# led.net
KiCad netlist of a schematic drawn in Altium Designer
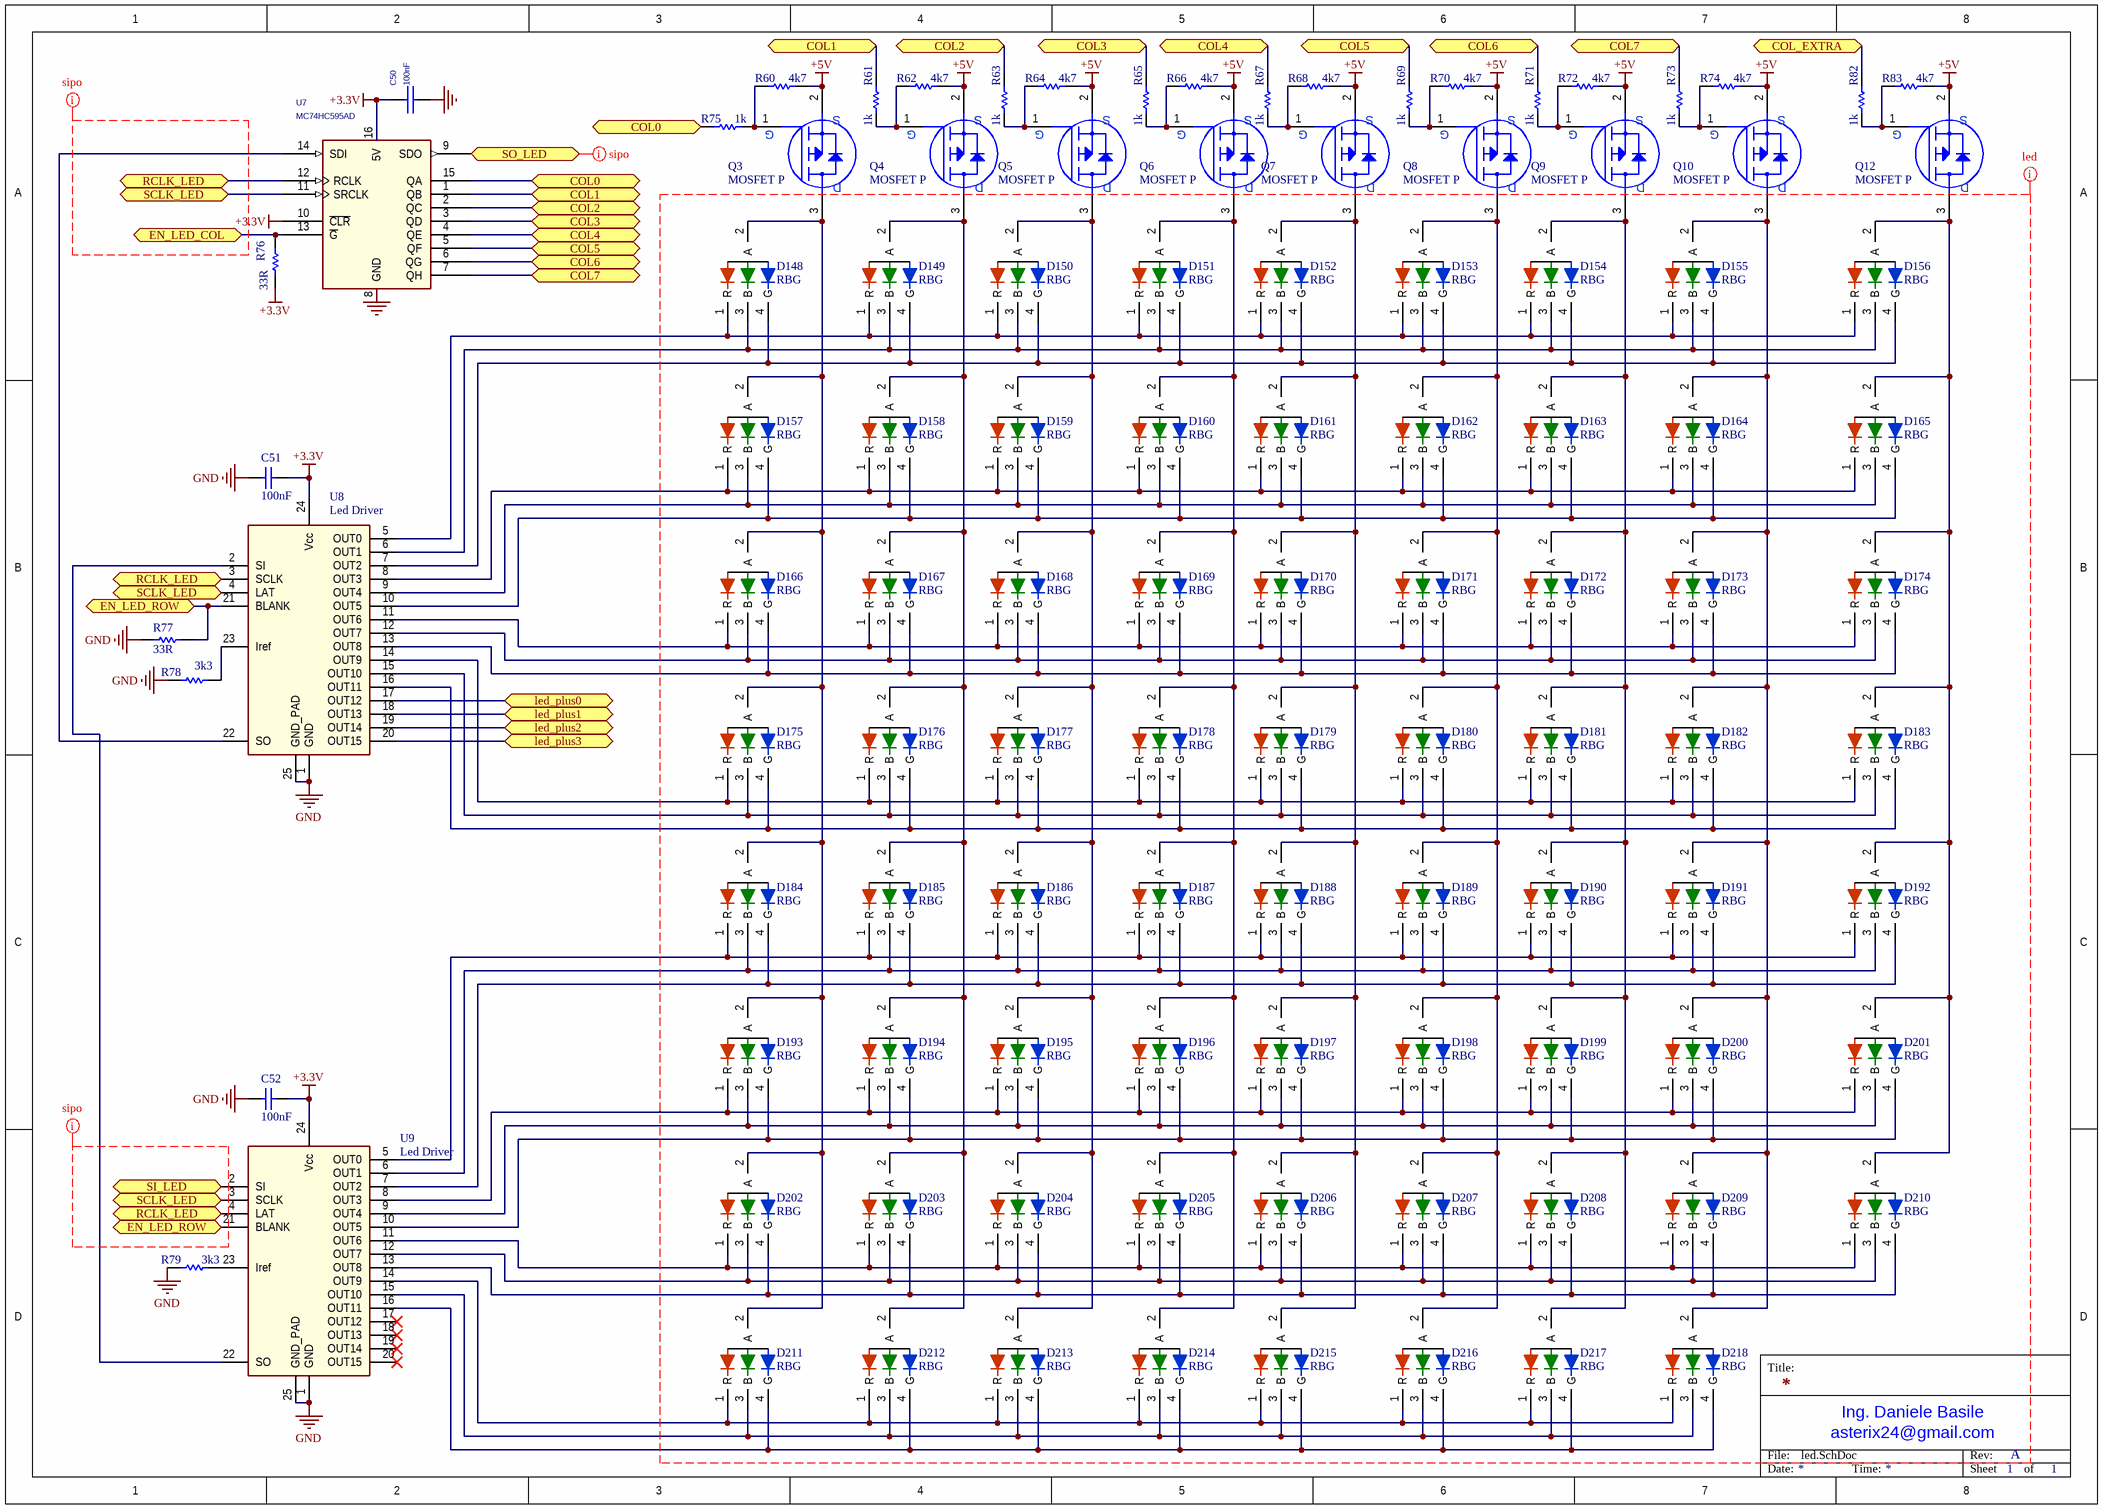
[diagram p0: led.SchDoc]

(export (version "E")
  (design (tool "Eeschema 10.0.6"))
  (components
    (comp (ref "C50")
      (value "100nF")
      (footprint "0603_[1608]")
      (description "CER 50V X7R")
      (libsource (lib "*") (part "C"))
    )
    (comp (ref "C51")
      (value "100nF")
      (footprint "0603_[1608]")
      (description "Ceramic X7R 50V")
      (fields (field (name "PUBLISHER") "Altium Limited"))
      (libsource (lib "DEVELER_Library") (part "Cap"))
    )
    (comp (ref "C52")
      (value "100nF")
      (footprint "0603_[1608]")
      (description "Ceramic X7R 50V")
      (fields (field (name "PUBLISHER") "Altium Limited"))
      (libsource (lib "DEVELER_Library") (part "Cap"))
    )
    (comp (ref "D148")
      (value "RBG")
      (description "Led RGB Thrue Hole")
      (libsource (lib "develer_library") (part "Led_RGB_COM_A_THD"))
    )
    (comp (ref "D149")
      (value "RBG")
      (footprint "led_3.2x2.8mm_4p_smd")
      (description "Led RGB Thrue Hole")
      (libsource (lib "develer_library") (part "Led_RGB_COM_A_THD"))
    )
    (comp (ref "D150")
      (value "RBG")
      (footprint "led_3.2x2.8mm_4p_smd")
      (description "Led RGB Thrue Hole")
      (libsource (lib "develer_library") (part "Led_RGB_COM_A_THD"))
    )
    (comp (ref "D151")
      (value "RBG")
      (footprint "led_3.2x2.8mm_4p_smd")
      (description "Led RGB Thrue Hole")
      (libsource (lib "develer_library") (part "Led_RGB_COM_A_THD"))
    )
    (comp (ref "D152")
      (value "RBG")
      (description "Led RGB Thrue Hole")
      (libsource (lib "develer_library") (part "Led_RGB_COM_A_THD"))
    )
    (comp (ref "D153")
      (value "RBG")
      (footprint "led_3.2x2.8mm_4p_smd")
      (description "Led RGB Thrue Hole")
      (libsource (lib "develer_library") (part "Led_RGB_COM_A_THD"))
    )
    (comp (ref "D154")
      (value "RBG")
      (description "Led RGB Thrue Hole")
      (libsource (lib "develer_library") (part "Led_RGB_COM_A_THD"))
    )
    (comp (ref "D155")
      (value "RBG")
      (description "Led RGB Thrue Hole")
      (libsource (lib "develer_library") (part "Led_RGB_COM_A_THD"))
    )
    (comp (ref "D156")
      (value "RBG")
      (footprint "R3_RGB_LED_THD")
      (description "Led RGB Thrue Hole")
      (libsource (lib "develer_library") (part "Led_RGB_COM_A_THD"))
    )
    (comp (ref "D157")
      (value "RBG")
      (footprint "R3_RGB_LED_THD")
      (description "Led RGB Thrue Hole")
      (libsource (lib "develer_library") (part "Led_RGB_COM_A_THD"))
    )
    (comp (ref "D158")
      (value "RBG")
      (footprint "R3_RGB_LED_THD")
      (description "Led RGB Thrue Hole")
      (libsource (lib "develer_library") (part "Led_RGB_COM_A_THD"))
    )
    (comp (ref "D159")
      (value "RBG")
      (footprint "R3_RGB_LED_THD")
      (description "Led RGB Thrue Hole")
      (libsource (lib "develer_library") (part "Led_RGB_COM_A_THD"))
    )
    (comp (ref "D160")
      (value "RBG")
      (description "Led RGB Thrue Hole")
      (libsource (lib "develer_library") (part "Led_RGB_COM_A_THD"))
    )
    (comp (ref "D161")
      (value "RBG")
      (description "Led RGB Thrue Hole")
      (libsource (lib "develer_library") (part "Led_RGB_COM_A_THD"))
    )
    (comp (ref "D162")
      (value "RBG")
      (description "Led RGB Thrue Hole")
      (libsource (lib "develer_library") (part "Led_RGB_COM_A_THD"))
    )
    (comp (ref "D163")
      (value "RBG")
      (description "Led RGB Thrue Hole")
      (libsource (lib "develer_library") (part "Led_RGB_COM_A_THD"))
    )
    (comp (ref "D164")
      (value "RBG")
      (footprint "led_3.2x2.8mm_4p_smd")
      (description "Led RGB Thrue Hole")
      (libsource (lib "develer_library") (part "Led_RGB_COM_A_THD"))
    )
    (comp (ref "D165")
      (value "RBG")
      (footprint "R3_RGB_LED_THD")
      (description "Led RGB Thrue Hole")
      (libsource (lib "develer_library") (part "Led_RGB_COM_A_THD"))
    )
    (comp (ref "D166")
      (value "RBG")
      (footprint "R3_RGB_LED_THD")
      (description "Led RGB Thrue Hole")
      (libsource (lib "develer_library") (part "Led_RGB_COM_A_THD"))
    )
    (comp (ref "D167")
      (value "RBG")
      (footprint "R3_RGB_LED_THD")
      (description "Led RGB Thrue Hole")
      (libsource (lib "develer_library") (part "Led_RGB_COM_A_THD"))
    )
    (comp (ref "D168")
      (value "RBG")
      (footprint "R3_RGB_LED_THD")
      (description "Led RGB Thrue Hole")
      (libsource (lib "develer_library") (part "Led_RGB_COM_A_THD"))
    )
    (comp (ref "D169")
      (value "RBG")
      (description "Led RGB Thrue Hole")
      (libsource (lib "develer_library") (part "Led_RGB_COM_A_THD"))
    )
    (comp (ref "D170")
      (value "RBG")
      (description "Led RGB Thrue Hole")
      (libsource (lib "develer_library") (part "Led_RGB_COM_A_THD"))
    )
    (comp (ref "D171")
      (value "RBG")
      (description "Led RGB Thrue Hole")
      (libsource (lib "develer_library") (part "Led_RGB_COM_A_THD"))
    )
    (comp (ref "D172")
      (value "RBG")
      (description "Led RGB Thrue Hole")
      (libsource (lib "develer_library") (part "Led_RGB_COM_A_THD"))
    )
    (comp (ref "D173")
      (value "RBG")
      (footprint "R3_RGB_LED_THD")
      (description "Led RGB Thrue Hole")
      (libsource (lib "develer_library") (part "Led_RGB_COM_A_THD"))
    )
    (comp (ref "D174")
      (value "RBG")
      (footprint "R3_RGB_LED_THD")
      (description "Led RGB Thrue Hole")
      (libsource (lib "develer_library") (part "Led_RGB_COM_A_THD"))
    )
    (comp (ref "D175")
      (value "RBG")
      (footprint "R3_RGB_LED_THD")
      (description "Led RGB Thrue Hole")
      (libsource (lib "develer_library") (part "Led_RGB_COM_A_THD"))
    )
    (comp (ref "D176")
      (value "RBG")
      (footprint "R3_RGB_LED_THD")
      (description "Led RGB Thrue Hole")
      (libsource (lib "develer_library") (part "Led_RGB_COM_A_THD"))
    )
    (comp (ref "D177")
      (value "RBG")
      (description "Led RGB Thrue Hole")
      (libsource (lib "develer_library") (part "Led_RGB_COM_A_THD"))
    )
    (comp (ref "D178")
      (value "RBG")
      (description "Led RGB Thrue Hole")
      (libsource (lib "develer_library") (part "Led_RGB_COM_A_THD"))
    )
    (comp (ref "D179")
      (value "RBG")
      (description "Led RGB Thrue Hole")
      (libsource (lib "develer_library") (part "Led_RGB_COM_A_THD"))
    )
    (comp (ref "D180")
      (value "RBG")
      (description "Led RGB Thrue Hole")
      (libsource (lib "develer_library") (part "Led_RGB_COM_A_THD"))
    )
    (comp (ref "D181")
      (value "RBG")
      (footprint "R3_RGB_LED_THD")
      (description "Led RGB Thrue Hole")
      (libsource (lib "develer_library") (part "Led_RGB_COM_A_THD"))
    )
    (comp (ref "D182")
      (value "RBG")
      (footprint "R3_RGB_LED_THD")
      (description "Led RGB Thrue Hole")
      (libsource (lib "develer_library") (part "Led_RGB_COM_A_THD"))
    )
    (comp (ref "D183")
      (value "RBG")
      (footprint "R3_RGB_LED_THD")
      (description "Led RGB Thrue Hole")
      (libsource (lib "develer_library") (part "Led_RGB_COM_A_THD"))
    )
    (comp (ref "D184")
      (value "RBG")
      (footprint "R3_RGB_LED_THD")
      (description "Led RGB Thrue Hole")
      (libsource (lib "develer_library") (part "Led_RGB_COM_A_THD"))
    )
    (comp (ref "D185")
      (value "RBG")
      (description "Led RGB Thrue Hole")
      (libsource (lib "develer_library") (part "Led_RGB_COM_A_THD"))
    )
    (comp (ref "D186")
      (value "RBG")
      (description "Led RGB Thrue Hole")
      (libsource (lib "develer_library") (part "Led_RGB_COM_A_THD"))
    )
    (comp (ref "D187")
      (value "RBG")
      (description "Led RGB Thrue Hole")
      (libsource (lib "develer_library") (part "Led_RGB_COM_A_THD"))
    )
    (comp (ref "D188")
      (value "RBG")
      (description "Led RGB Thrue Hole")
      (libsource (lib "develer_library") (part "Led_RGB_COM_A_THD"))
    )
    (comp (ref "D189")
      (value "RBG")
      (footprint "R3_RGB_LED_THD")
      (description "Led RGB Thrue Hole")
      (libsource (lib "develer_library") (part "Led_RGB_COM_A_THD"))
    )
    (comp (ref "D190")
      (value "RBG")
      (footprint "R3_RGB_LED_THD")
      (description "Led RGB Thrue Hole")
      (libsource (lib "develer_library") (part "Led_RGB_COM_A_THD"))
    )
    (comp (ref "D191")
      (value "RBG")
      (footprint "R3_RGB_LED_THD")
      (description "Led RGB Thrue Hole")
      (libsource (lib "develer_library") (part "Led_RGB_COM_A_THD"))
    )
    (comp (ref "D192")
      (value "RBG")
      (footprint "R3_RGB_LED_THD")
      (description "Led RGB Thrue Hole")
      (libsource (lib "develer_library") (part "Led_RGB_COM_A_THD"))
    )
    (comp (ref "D193")
      (value "RBG")
      (description "Led RGB Thrue Hole")
      (libsource (lib "develer_library") (part "Led_RGB_COM_A_THD"))
    )
    (comp (ref "D194")
      (value "RBG")
      (description "Led RGB Thrue Hole")
      (libsource (lib "develer_library") (part "Led_RGB_COM_A_THD"))
    )
    (comp (ref "D195")
      (value "RBG")
      (description "Led RGB Thrue Hole")
      (libsource (lib "develer_library") (part "Led_RGB_COM_A_THD"))
    )
    (comp (ref "D196")
      (value "RBG")
      (description "Led RGB Thrue Hole")
      (libsource (lib "develer_library") (part "Led_RGB_COM_A_THD"))
    )
    (comp (ref "D197")
      (value "RBG")
      (footprint "R3_RGB_LED_THD")
      (description "Led RGB Thrue Hole")
      (libsource (lib "develer_library") (part "Led_RGB_COM_A_THD"))
    )
    (comp (ref "D198")
      (value "RBG")
      (footprint "R3_RGB_LED_THD")
      (description "Led RGB Thrue Hole")
      (libsource (lib "develer_library") (part "Led_RGB_COM_A_THD"))
    )
    (comp (ref "D199")
      (value "RBG")
      (footprint "R3_RGB_LED_THD")
      (description "Led RGB Thrue Hole")
      (libsource (lib "develer_library") (part "Led_RGB_COM_A_THD"))
    )
    (comp (ref "D200")
      (value "RBG")
      (footprint "led_3.2x2.8mm_4p_smd")
      (description "Led RGB Thrue Hole")
      (libsource (lib "develer_library") (part "Led_RGB_COM_A_THD"))
    )
    (comp (ref "D201")
      (value "RBG")
      (footprint "R3_RGB_LED_THD")
      (description "Led RGB Thrue Hole")
      (libsource (lib "develer_library") (part "Led_RGB_COM_A_THD"))
    )
    (comp (ref "D202")
      (value "RBG")
      (description "Led RGB Thrue Hole")
      (libsource (lib "develer_library") (part "Led_RGB_COM_A_THD"))
    )
    (comp (ref "D203")
      (value "RBG")
      (description "Led RGB Thrue Hole")
      (libsource (lib "develer_library") (part "Led_RGB_COM_A_THD"))
    )
    (comp (ref "D204")
      (value "RBG")
      (description "Led RGB Thrue Hole")
      (libsource (lib "develer_library") (part "Led_RGB_COM_A_THD"))
    )
    (comp (ref "D205")
      (value "RBG")
      (description "Led RGB Thrue Hole")
      (libsource (lib "develer_library") (part "Led_RGB_COM_A_THD"))
    )
    (comp (ref "D206")
      (value "RBG")
      (footprint "R3_RGB_LED_THD")
      (description "Led RGB Thrue Hole")
      (libsource (lib "develer_library") (part "Led_RGB_COM_A_THD"))
    )
    (comp (ref "D207")
      (value "RBG")
      (footprint "R3_RGB_LED_THD")
      (description "Led RGB Thrue Hole")
      (libsource (lib "develer_library") (part "Led_RGB_COM_A_THD"))
    )
    (comp (ref "D208")
      (value "RBG")
      (footprint "R3_RGB_LED_THD")
      (description "Led RGB Thrue Hole")
      (libsource (lib "develer_library") (part "Led_RGB_COM_A_THD"))
    )
    (comp (ref "D209")
      (value "RBG")
      (footprint "R3_RGB_LED_THD")
      (description "Led RGB Thrue Hole")
      (libsource (lib "develer_library") (part "Led_RGB_COM_A_THD"))
    )
    (comp (ref "D210")
      (value "RBG")
      (description "Led RGB Thrue Hole")
      (libsource (lib "develer_library") (part "Led_RGB_COM_A_THD"))
    )
    (comp (ref "D211")
      (value "RBG")
      (description "Led RGB Thrue Hole")
      (libsource (lib "develer_library") (part "Led_RGB_COM_A_THD"))
    )
    (comp (ref "D212")
      (value "RBG")
      (footprint "R3_RGB_LED_THD")
      (description "Led RGB Thrue Hole")
      (libsource (lib "develer_library") (part "Led_RGB_COM_A_THD"))
    )
    (comp (ref "D213")
      (value "RBG")
      (footprint "R3_RGB_LED_THD")
      (description "Led RGB Thrue Hole")
      (libsource (lib "develer_library") (part "Led_RGB_COM_A_THD"))
    )
    (comp (ref "D214")
      (value "RBG")
      (footprint "R3_RGB_LED_THD")
      (description "Led RGB Thrue Hole")
      (libsource (lib "develer_library") (part "Led_RGB_COM_A_THD"))
    )
    (comp (ref "D215")
      (value "RBG")
      (footprint "R3_RGB_LED_THD")
      (description "Led RGB Thrue Hole")
      (libsource (lib "develer_library") (part "Led_RGB_COM_A_THD"))
    )
    (comp (ref "D216")
      (value "RBG")
      (footprint "R3_RGB_LED_THD")
      (description "Led RGB Thrue Hole")
      (libsource (lib "develer_library") (part "Led_RGB_COM_A_THD"))
    )
    (comp (ref "D217")
      (value "RBG")
      (footprint "R3_RGB_LED_THD")
      (description "Led RGB Thrue Hole")
      (libsource (lib "develer_library") (part "Led_RGB_COM_A_THD"))
    )
    (comp (ref "D218")
      (value "RBG")
      (footprint "R3_RGB_LED_THD")
      (description "Led RGB Thrue Hole")
      (libsource (lib "develer_library") (part "Led_RGB_COM_A_THD"))
    )
    (comp (ref "Q3")
      (value "MOSFET P")
      (footprint "SOT-23")
      (description "IRLML5103TRPbF; DMG1013UW;")
      (libsource (lib "develer_library") (part "MOSFET-P 3pin"))
    )
    (comp (ref "Q4")
      (value "MOSFET P")
      (footprint "SOT-23")
      (libsource (lib "develer_library") (part "MOSFET-P 3pin"))
    )
    (comp (ref "Q5")
      (value "MOSFET P")
      (footprint "SOT-23")
      (libsource (lib "develer_library") (part "MOSFET-P 3pin"))
    )
    (comp (ref "Q6")
      (value "MOSFET P")
      (footprint "SOT-23")
      (libsource (lib "develer_library") (part "MOSFET-P 3pin"))
    )
    (comp (ref "Q7")
      (value "MOSFET P")
      (footprint "SOT-23")
      (libsource (lib "develer_library") (part "MOSFET-P 3pin"))
    )
    (comp (ref "Q8")
      (value "MOSFET P")
      (footprint "SOT-23")
      (libsource (lib "develer_library") (part "MOSFET-P 3pin"))
    )
    (comp (ref "Q9")
      (value "MOSFET P")
      (footprint "SOT-23")
      (libsource (lib "develer_library") (part "MOSFET-P 3pin"))
    )
    (comp (ref "Q10")
      (value "MOSFET P")
      (footprint "SOT-23")
      (libsource (lib "develer_library") (part "MOSFET-P 3pin"))
    )
    (comp (ref "Q12")
      (value "MOSFET P")
      (footprint "SOT-23")
      (libsource (lib "develer_library") (part "MOSFET-P 3pin"))
    )
    (comp (ref "R60")
      (value "4k7")
      (footprint "0603_[1608]")
      (description "Resistor")
      (fields (field (name "PUBLISHER") "Altium Limited"))
      (libsource (lib "simboli") (part "Res1"))
    )
    (comp (ref "R61")
      (value "1k")
      (footprint "0603_[1608]")
      (description "Resistor")
      (fields (field (name "PUBLISHER") "Altium Limited"))
      (libsource (lib "simboli") (part "Res1"))
    )
    (comp (ref "R62")
      (value "4k7")
      (footprint "0603_[1608]")
      (description "Resistor")
      (fields (field (name "PUBLISHER") "Altium Limited"))
      (libsource (lib "simboli") (part "Res1"))
    )
    (comp (ref "R63")
      (value "1k")
      (footprint "0603_[1608]")
      (description "Resistor")
      (fields (field (name "PUBLISHER") "Altium Limited"))
      (libsource (lib "simboli") (part "Res1"))
    )
    (comp (ref "R64")
      (value "4k7")
      (footprint "0603_[1608]")
      (description "Resistor")
      (fields (field (name "PUBLISHER") "Altium Limited"))
      (libsource (lib "simboli") (part "Res1"))
    )
    (comp (ref "R65")
      (value "1k")
      (footprint "0603_[1608]")
      (description "Resistor")
      (fields (field (name "PUBLISHER") "Altium Limited"))
      (libsource (lib "simboli") (part "Res1"))
    )
    (comp (ref "R66")
      (value "4k7")
      (footprint "0603_[1608]")
      (description "Resistor")
      (fields (field (name "PUBLISHER") "Altium Limited"))
      (libsource (lib "simboli") (part "Res1"))
    )
    (comp (ref "R67")
      (value "1k")
      (footprint "0603_[1608]")
      (description "Resistor")
      (fields (field (name "PUBLISHER") "Altium Limited"))
      (libsource (lib "simboli") (part "Res1"))
    )
    (comp (ref "R68")
      (value "4k7")
      (footprint "0603_[1608]")
      (description "Resistor")
      (fields (field (name "PUBLISHER") "Altium Limited"))
      (libsource (lib "simboli") (part "Res1"))
    )
    (comp (ref "R69")
      (value "1k")
      (footprint "0603_[1608]")
      (description "Resistor")
      (fields (field (name "PUBLISHER") "Altium Limited"))
      (libsource (lib "simboli") (part "Res1"))
    )
    (comp (ref "R70")
      (value "4k7")
      (footprint "0603_[1608]")
      (description "Resistor")
      (fields (field (name "PUBLISHER") "Altium Limited"))
      (libsource (lib "simboli") (part "Res1"))
    )
    (comp (ref "R71")
      (value "1k")
      (footprint "0603_[1608]")
      (description "Resistor")
      (fields (field (name "PUBLISHER") "Altium Limited"))
      (libsource (lib "simboli") (part "Res1"))
    )
    (comp (ref "R72")
      (value "4k7")
      (footprint "0603_[1608]")
      (description "Resistor")
      (fields (field (name "PUBLISHER") "Altium Limited"))
      (libsource (lib "simboli") (part "Res1"))
    )
    (comp (ref "R73")
      (value "1k")
      (footprint "0603_[1608]")
      (description "Resistor")
      (fields (field (name "PUBLISHER") "Altium Limited"))
      (libsource (lib "simboli") (part "Res1"))
    )
    (comp (ref "R74")
      (value "4k7")
      (footprint "0603_[1608]")
      (description "Resistor")
      (fields (field (name "PUBLISHER") "Altium Limited"))
      (libsource (lib "simboli") (part "Res1"))
    )
    (comp (ref "R75")
      (value "1k")
      (footprint "0603_[1608]")
      (description "Resistor")
      (fields (field (name "PUBLISHER") "Altium Limited"))
      (libsource (lib "simboli") (part "Res1"))
    )
    (comp (ref "R76")
      (value "33R")
      (footprint "0603_[1608]")
      (description "Resistor")
      (fields (field (name "PUBLISHER") "Altium Limited"))
      (libsource (lib "simboli") (part "Res1"))
    )
    (comp (ref "R77")
      (value "33R")
      (footprint "0603_[1608]")
      (description "Resistor")
      (fields (field (name "PUBLISHER") "Altium Limited"))
      (libsource (lib "simboli") (part "Res1"))
    )
    (comp (ref "R78")
      (value "3k3")
      (footprint "0805_[2012]")
      (description "Resistor")
      (fields (field (name "PUBLISHER") "Altium Limited"))
      (libsource (lib "simboli") (part "Res1"))
    )
    (comp (ref "R79")
      (value "3k3")
      (footprint "0805_[2012]")
      (description "Resistor")
      (fields (field (name "PUBLISHER") "Altium Limited"))
      (libsource (lib "simboli") (part "Res1"))
    )
    (comp (ref "R82")
      (value "1k")
      (footprint "0603_[1608]")
      (description "Resistor")
      (fields (field (name "PUBLISHER") "Altium Limited"))
      (libsource (lib "simboli") (part "Res1"))
    )
    (comp (ref "R83")
      (value "4k7")
      (footprint "0603_[1608]")
      (description "Resistor")
      (fields (field (name "PUBLISHER") "Altium Limited"))
      (libsource (lib "simboli") (part "Res1"))
    )
    (comp (ref "U7")
      (value "MC74HC595AD")
      (footprint "SOIC16")
      (description "8-Bit Serial-Input/Serial or Prallel-Output Shift Register with Latched 3-State Outputs")
      (libsource (lib "*") (part "74HC595_27"))
    )
    (comp (ref "U8")
      (value "Led Driver")
      (footprint "TSOP65P640X120_HS-25N")
      (description "(Texas TLC5928; ST STP16CP05)")
      (libsource (lib "develer_library") (part "Led_driver"))
    )
    (comp (ref "U9")
      (value "Led Driver")
      (footprint "TSOP65P640X120_HS-25N")
      (description "(Texas TLC5928; ST STP16CP05)")
      (libsource (lib "develer_library") (part "Led_driver"))
    )
  )
  (nets
    (net (code "1") (name "+3.3V") (class "Default")
      (node (ref "C50") (pin "1") (pinfunction "1_1") (pintype "passive"))
      (node (ref "C51") (pin "2") (pinfunction "2_2") (pintype "passive"))
      (node (ref "C52") (pin "2") (pinfunction "2_2") (pintype "passive"))
      (node (ref "R76") (pin "1") (pinfunction "1_1") (pintype "passive"))
      (node (ref "U7") (pin "10") (pinfunction "~{CLR}_10") (pintype "passive"))
      (node (ref "U7") (pin "16") (pinfunction "5V_16") (pintype "power_in"))
      (node (ref "U8") (pin "24") (pinfunction "Vcc_24") (pintype "passive"))
      (node (ref "U9") (pin "24") (pinfunction "Vcc_24") (pintype "passive"))
    )
    (net (code "2") (name "+5V") (class "Default")
      (node (ref "Q10") (pin "2") (pinfunction "S_2") (pintype "passive"))
      (node (ref "Q12") (pin "2") (pinfunction "S_2") (pintype "passive"))
      (node (ref "Q3") (pin "2") (pinfunction "S_2") (pintype "passive"))
      (node (ref "Q4") (pin "2") (pinfunction "S_2") (pintype "passive"))
      (node (ref "Q5") (pin "2") (pinfunction "S_2") (pintype "passive"))
      (node (ref "Q6") (pin "2") (pinfunction "S_2") (pintype "passive"))
      (node (ref "Q7") (pin "2") (pinfunction "S_2") (pintype "passive"))
      (node (ref "Q8") (pin "2") (pinfunction "S_2") (pintype "passive"))
      (node (ref "Q9") (pin "2") (pinfunction "S_2") (pintype "passive"))
      (node (ref "R60") (pin "1") (pinfunction "1_1") (pintype "passive"))
      (node (ref "R62") (pin "1") (pinfunction "1_1") (pintype "passive"))
      (node (ref "R64") (pin "1") (pinfunction "1_1") (pintype "passive"))
      (node (ref "R66") (pin "1") (pinfunction "1_1") (pintype "passive"))
      (node (ref "R68") (pin "1") (pinfunction "1_1") (pintype "passive"))
      (node (ref "R70") (pin "1") (pinfunction "1_1") (pintype "passive"))
      (node (ref "R72") (pin "1") (pinfunction "1_1") (pintype "passive"))
      (node (ref "R74") (pin "1") (pinfunction "1_1") (pintype "passive"))
      (node (ref "R83") (pin "1") (pinfunction "1_1") (pintype "passive"))
    )
    (net (code "3") (name "/COL0") (class "Default")
      (node (ref "R75") (pin "2") (pinfunction "2_2") (pintype "passive"))
      (node (ref "U7") (pin "15") (pinfunction "QA_15") (pintype "tri_state"))
    )
    (net (code "4") (name "/COL1") (class "Default")
      (node (ref "R61") (pin "1") (pinfunction "1_1") (pintype "passive"))
      (node (ref "U7") (pin "1") (pinfunction "QB_1") (pintype "tri_state"))
    )
    (net (code "5") (name "/COL2") (class "Default")
      (node (ref "R63") (pin "1") (pinfunction "1_1") (pintype "passive"))
      (node (ref "U7") (pin "2") (pinfunction "QC_2") (pintype "tri_state"))
    )
    (net (code "6") (name "/COL3") (class "Default")
      (node (ref "R65") (pin "1") (pinfunction "1_1") (pintype "passive"))
      (node (ref "U7") (pin "3") (pinfunction "QD_3") (pintype "tri_state"))
    )
    (net (code "7") (name "/COL4") (class "Default")
      (node (ref "R67") (pin "1") (pinfunction "1_1") (pintype "passive"))
      (node (ref "U7") (pin "4") (pinfunction "QE_4") (pintype "tri_state"))
    )
    (net (code "8") (name "/COL5") (class "Default")
      (node (ref "R69") (pin "1") (pinfunction "1_1") (pintype "passive"))
      (node (ref "U7") (pin "5") (pinfunction "QF_5") (pintype "tri_state"))
    )
    (net (code "9") (name "/COL6") (class "Default")
      (node (ref "R71") (pin "1") (pinfunction "1_1") (pintype "passive"))
      (node (ref "U7") (pin "6") (pinfunction "QG_6") (pintype "tri_state"))
    )
    (net (code "10") (name "/COL7") (class "Default")
      (node (ref "R73") (pin "1") (pinfunction "1_1") (pintype "passive"))
      (node (ref "U7") (pin "7") (pinfunction "QH_7") (pintype "tri_state"))
    )
    (net (code "11") (name "/COL_EXTRA") (class "Default")
      (node (ref "R82") (pin "1") (pinfunction "1_1") (pintype "passive"))
    )
    (net (code "12") (name "/EN_LED_COL") (class "Default")
      (node (ref "R76") (pin "2") (pinfunction "2_2") (pintype "passive"))
      (node (ref "U7") (pin "13") (pinfunction "~{G}_13") (pintype "passive"))
    )
    (net (code "13") (name "/EN_LED_ROW") (class "Default")
      (node (ref "R77") (pin "2") (pinfunction "2_2") (pintype "passive"))
      (node (ref "U8") (pin "21") (pinfunction "BLANK_21") (pintype "passive"))
      (node (ref "U9") (pin "21") (pinfunction "BLANK_21") (pintype "passive"))
    )
    (net (code "14") (name "/RCLK_LED") (class "Default")
      (node (ref "U7") (pin "12") (pinfunction "RCLK_12") (pintype "input"))
      (node (ref "U8") (pin "3") (pinfunction "SCLK_3") (pintype "passive"))
      (node (ref "U9") (pin "4") (pinfunction "LAT_4") (pintype "passive"))
    )
    (net (code "15") (name "/SCLK_LED") (class "Default")
      (node (ref "U7") (pin "11") (pinfunction "SRCLK_11") (pintype "input"))
      (node (ref "U8") (pin "4") (pinfunction "LAT_4") (pintype "passive"))
      (node (ref "U9") (pin "3") (pinfunction "SCLK_3") (pintype "passive"))
    )
    (net (code "16") (name "/SI_LED") (class "Default")
      (node (ref "U9") (pin "2") (pinfunction "SI_2") (pintype "passive"))
    )
    (net (code "17") (name "/SO_LED") (class "Default")
      (node (ref "U7") (pin "9") (pinfunction "SDO_9") (pintype "output"))
    )
    (net (code "18") (name "/led_plus0") (class "Default")
      (node (ref "U8") (pin "17") (pinfunction "OUT12_17") (pintype "passive"))
    )
    (net (code "19") (name "/led_plus1") (class "Default")
      (node (ref "U8") (pin "18") (pinfunction "OUT13_18") (pintype "passive"))
    )
    (net (code "20") (name "/led_plus2") (class "Default")
      (node (ref "U8") (pin "19") (pinfunction "OUT14_19") (pintype "passive"))
    )
    (net (code "21") (name "/led_plus3") (class "Default")
      (node (ref "U8") (pin "20") (pinfunction "OUT15_20") (pintype "passive"))
    )
    (net (code "22") (name "GND") (class "Default")
      (node (ref "C50") (pin "2") (pinfunction "2_2") (pintype "passive"))
      (node (ref "C51") (pin "1") (pinfunction "1_1") (pintype "passive"))
      (node (ref "C52") (pin "1") (pinfunction "1_1") (pintype "passive"))
      (node (ref "R77") (pin "1") (pinfunction "1_1") (pintype "passive"))
      (node (ref "R78") (pin "1") (pinfunction "1_1") (pintype "passive"))
      (node (ref "R79") (pin "1") (pinfunction "1_1") (pintype "passive"))
      (node (ref "U7") (pin "8") (pinfunction "GND_8") (pintype "power_in"))
      (node (ref "U8") (pin "1") (pinfunction "GND_1") (pintype "passive"))
      (node (ref "U8") (pin "25") (pinfunction "GND_PAD_25") (pintype "passive"))
      (node (ref "U9") (pin "1") (pinfunction "GND_1") (pintype "passive"))
      (node (ref "U9") (pin "25") (pinfunction "GND_PAD_25") (pintype "passive"))
    )
    (net (code "23") (name "Net-(D148-A)") (class "Default")
      (node (ref "D148") (pin "2") (pinfunction "A_2") (pintype "passive"))
      (node (ref "D157") (pin "2") (pinfunction "A_2") (pintype "passive"))
      (node (ref "D166") (pin "2") (pinfunction "A_2") (pintype "passive"))
      (node (ref "D175") (pin "2") (pinfunction "A_2") (pintype "passive"))
      (node (ref "D184") (pin "2") (pinfunction "A_2") (pintype "passive"))
      (node (ref "D193") (pin "2") (pinfunction "A_2") (pintype "passive"))
      (node (ref "D202") (pin "2") (pinfunction "A_2") (pintype "passive"))
      (node (ref "D211") (pin "2") (pinfunction "A_2") (pintype "passive"))
      (node (ref "Q3") (pin "3") (pinfunction "D_3") (pintype "passive"))
    )
    (net (code "24") (name "Net-(D148-B)") (class "Default")
      (node (ref "D148") (pin "3") (pinfunction "B_3") (pintype "passive"))
      (node (ref "D149") (pin "3") (pinfunction "B_3") (pintype "passive"))
      (node (ref "D150") (pin "3") (pinfunction "B_3") (pintype "passive"))
      (node (ref "D151") (pin "3") (pinfunction "B_3") (pintype "passive"))
      (node (ref "D152") (pin "3") (pinfunction "B_3") (pintype "passive"))
      (node (ref "D153") (pin "3") (pinfunction "B_3") (pintype "passive"))
      (node (ref "D154") (pin "3") (pinfunction "B_3") (pintype "passive"))
      (node (ref "D155") (pin "3") (pinfunction "B_3") (pintype "passive"))
      (node (ref "D156") (pin "3") (pinfunction "B_3") (pintype "passive"))
      (node (ref "U8") (pin "6") (pinfunction "OUT1_6") (pintype "passive"))
    )
    (net (code "25") (name "Net-(D148-G)") (class "Default")
      (node (ref "D148") (pin "4") (pinfunction "G_4") (pintype "passive"))
      (node (ref "D149") (pin "4") (pinfunction "G_4") (pintype "passive"))
      (node (ref "D150") (pin "4") (pinfunction "G_4") (pintype "passive"))
      (node (ref "D151") (pin "4") (pinfunction "G_4") (pintype "passive"))
      (node (ref "D152") (pin "4") (pinfunction "G_4") (pintype "passive"))
      (node (ref "D153") (pin "4") (pinfunction "G_4") (pintype "passive"))
      (node (ref "D154") (pin "4") (pinfunction "G_4") (pintype "passive"))
      (node (ref "D155") (pin "4") (pinfunction "G_4") (pintype "passive"))
      (node (ref "D156") (pin "4") (pinfunction "G_4") (pintype "passive"))
      (node (ref "U8") (pin "7") (pinfunction "OUT2_7") (pintype "passive"))
    )
    (net (code "26") (name "Net-(D148-R)") (class "Default")
      (node (ref "D148") (pin "1") (pinfunction "R_1") (pintype "passive"))
      (node (ref "D149") (pin "1") (pinfunction "R_1") (pintype "passive"))
      (node (ref "D150") (pin "1") (pinfunction "R_1") (pintype "passive"))
      (node (ref "D151") (pin "1") (pinfunction "R_1") (pintype "passive"))
      (node (ref "D152") (pin "1") (pinfunction "R_1") (pintype "passive"))
      (node (ref "D153") (pin "1") (pinfunction "R_1") (pintype "passive"))
      (node (ref "D154") (pin "1") (pinfunction "R_1") (pintype "passive"))
      (node (ref "D155") (pin "1") (pinfunction "R_1") (pintype "passive"))
      (node (ref "D156") (pin "1") (pinfunction "R_1") (pintype "passive"))
      (node (ref "U8") (pin "5") (pinfunction "OUT0_5") (pintype "passive"))
    )
    (net (code "27") (name "Net-(D149-A)") (class "Default")
      (node (ref "D149") (pin "2") (pinfunction "A_2") (pintype "passive"))
      (node (ref "D158") (pin "2") (pinfunction "A_2") (pintype "passive"))
      (node (ref "D167") (pin "2") (pinfunction "A_2") (pintype "passive"))
      (node (ref "D176") (pin "2") (pinfunction "A_2") (pintype "passive"))
      (node (ref "D185") (pin "2") (pinfunction "A_2") (pintype "passive"))
      (node (ref "D194") (pin "2") (pinfunction "A_2") (pintype "passive"))
      (node (ref "D203") (pin "2") (pinfunction "A_2") (pintype "passive"))
      (node (ref "D212") (pin "2") (pinfunction "A_2") (pintype "passive"))
      (node (ref "Q4") (pin "3") (pinfunction "D_3") (pintype "passive"))
    )
    (net (code "28") (name "Net-(D150-A)") (class "Default")
      (node (ref "D150") (pin "2") (pinfunction "A_2") (pintype "passive"))
      (node (ref "D159") (pin "2") (pinfunction "A_2") (pintype "passive"))
      (node (ref "D168") (pin "2") (pinfunction "A_2") (pintype "passive"))
      (node (ref "D177") (pin "2") (pinfunction "A_2") (pintype "passive"))
      (node (ref "D186") (pin "2") (pinfunction "A_2") (pintype "passive"))
      (node (ref "D195") (pin "2") (pinfunction "A_2") (pintype "passive"))
      (node (ref "D204") (pin "2") (pinfunction "A_2") (pintype "passive"))
      (node (ref "D213") (pin "2") (pinfunction "A_2") (pintype "passive"))
      (node (ref "Q5") (pin "3") (pinfunction "D_3") (pintype "passive"))
    )
    (net (code "29") (name "Net-(D151-A)") (class "Default")
      (node (ref "D151") (pin "2") (pinfunction "A_2") (pintype "passive"))
      (node (ref "D160") (pin "2") (pinfunction "A_2") (pintype "passive"))
      (node (ref "D169") (pin "2") (pinfunction "A_2") (pintype "passive"))
      (node (ref "D178") (pin "2") (pinfunction "A_2") (pintype "passive"))
      (node (ref "D187") (pin "2") (pinfunction "A_2") (pintype "passive"))
      (node (ref "D196") (pin "2") (pinfunction "A_2") (pintype "passive"))
      (node (ref "D205") (pin "2") (pinfunction "A_2") (pintype "passive"))
      (node (ref "D214") (pin "2") (pinfunction "A_2") (pintype "passive"))
      (node (ref "Q6") (pin "3") (pinfunction "D_3") (pintype "passive"))
    )
    (net (code "30") (name "Net-(D152-A)") (class "Default")
      (node (ref "D152") (pin "2") (pinfunction "A_2") (pintype "passive"))
      (node (ref "D161") (pin "2") (pinfunction "A_2") (pintype "passive"))
      (node (ref "D170") (pin "2") (pinfunction "A_2") (pintype "passive"))
      (node (ref "D179") (pin "2") (pinfunction "A_2") (pintype "passive"))
      (node (ref "D188") (pin "2") (pinfunction "A_2") (pintype "passive"))
      (node (ref "D197") (pin "2") (pinfunction "A_2") (pintype "passive"))
      (node (ref "D206") (pin "2") (pinfunction "A_2") (pintype "passive"))
      (node (ref "D215") (pin "2") (pinfunction "A_2") (pintype "passive"))
      (node (ref "Q7") (pin "3") (pinfunction "D_3") (pintype "passive"))
    )
    (net (code "31") (name "Net-(D153-A)") (class "Default")
      (node (ref "D153") (pin "2") (pinfunction "A_2") (pintype "passive"))
      (node (ref "D162") (pin "2") (pinfunction "A_2") (pintype "passive"))
      (node (ref "D171") (pin "2") (pinfunction "A_2") (pintype "passive"))
      (node (ref "D180") (pin "2") (pinfunction "A_2") (pintype "passive"))
      (node (ref "D189") (pin "2") (pinfunction "A_2") (pintype "passive"))
      (node (ref "D198") (pin "2") (pinfunction "A_2") (pintype "passive"))
      (node (ref "D207") (pin "2") (pinfunction "A_2") (pintype "passive"))
      (node (ref "D216") (pin "2") (pinfunction "A_2") (pintype "passive"))
      (node (ref "Q8") (pin "3") (pinfunction "D_3") (pintype "passive"))
    )
    (net (code "32") (name "Net-(D154-A)") (class "Default")
      (node (ref "D154") (pin "2") (pinfunction "A_2") (pintype "passive"))
      (node (ref "D163") (pin "2") (pinfunction "A_2") (pintype "passive"))
      (node (ref "D172") (pin "2") (pinfunction "A_2") (pintype "passive"))
      (node (ref "D181") (pin "2") (pinfunction "A_2") (pintype "passive"))
      (node (ref "D190") (pin "2") (pinfunction "A_2") (pintype "passive"))
      (node (ref "D199") (pin "2") (pinfunction "A_2") (pintype "passive"))
      (node (ref "D208") (pin "2") (pinfunction "A_2") (pintype "passive"))
      (node (ref "D217") (pin "2") (pinfunction "A_2") (pintype "passive"))
      (node (ref "Q9") (pin "3") (pinfunction "D_3") (pintype "passive"))
    )
    (net (code "33") (name "Net-(D155-A)") (class "Default")
      (node (ref "D155") (pin "2") (pinfunction "A_2") (pintype "passive"))
      (node (ref "D164") (pin "2") (pinfunction "A_2") (pintype "passive"))
      (node (ref "D173") (pin "2") (pinfunction "A_2") (pintype "passive"))
      (node (ref "D182") (pin "2") (pinfunction "A_2") (pintype "passive"))
      (node (ref "D191") (pin "2") (pinfunction "A_2") (pintype "passive"))
      (node (ref "D200") (pin "2") (pinfunction "A_2") (pintype "passive"))
      (node (ref "D209") (pin "2") (pinfunction "A_2") (pintype "passive"))
      (node (ref "D218") (pin "2") (pinfunction "A_2") (pintype "passive"))
      (node (ref "Q10") (pin "3") (pinfunction "D_3") (pintype "passive"))
    )
    (net (code "34") (name "Net-(D156-A)") (class "Default")
      (node (ref "D156") (pin "2") (pinfunction "A_2") (pintype "passive"))
      (node (ref "D165") (pin "2") (pinfunction "A_2") (pintype "passive"))
      (node (ref "D174") (pin "2") (pinfunction "A_2") (pintype "passive"))
      (node (ref "D183") (pin "2") (pinfunction "A_2") (pintype "passive"))
      (node (ref "D192") (pin "2") (pinfunction "A_2") (pintype "passive"))
      (node (ref "D201") (pin "2") (pinfunction "A_2") (pintype "passive"))
      (node (ref "D210") (pin "2") (pinfunction "A_2") (pintype "passive"))
      (node (ref "Q12") (pin "3") (pinfunction "D_3") (pintype "passive"))
    )
    (net (code "35") (name "Net-(D157-B)") (class "Default")
      (node (ref "D157") (pin "3") (pinfunction "B_3") (pintype "passive"))
      (node (ref "D158") (pin "3") (pinfunction "B_3") (pintype "passive"))
      (node (ref "D159") (pin "3") (pinfunction "B_3") (pintype "passive"))
      (node (ref "D160") (pin "3") (pinfunction "B_3") (pintype "passive"))
      (node (ref "D161") (pin "3") (pinfunction "B_3") (pintype "passive"))
      (node (ref "D162") (pin "3") (pinfunction "B_3") (pintype "passive"))
      (node (ref "D163") (pin "3") (pinfunction "B_3") (pintype "passive"))
      (node (ref "D164") (pin "3") (pinfunction "B_3") (pintype "passive"))
      (node (ref "D165") (pin "3") (pinfunction "B_3") (pintype "passive"))
      (node (ref "U8") (pin "9") (pinfunction "OUT4_9") (pintype "passive"))
    )
    (net (code "36") (name "Net-(D157-G)") (class "Default")
      (node (ref "D157") (pin "4") (pinfunction "G_4") (pintype "passive"))
      (node (ref "D158") (pin "4") (pinfunction "G_4") (pintype "passive"))
      (node (ref "D159") (pin "4") (pinfunction "G_4") (pintype "passive"))
      (node (ref "D160") (pin "4") (pinfunction "G_4") (pintype "passive"))
      (node (ref "D161") (pin "4") (pinfunction "G_4") (pintype "passive"))
      (node (ref "D162") (pin "4") (pinfunction "G_4") (pintype "passive"))
      (node (ref "D163") (pin "4") (pinfunction "G_4") (pintype "passive"))
      (node (ref "D164") (pin "4") (pinfunction "G_4") (pintype "passive"))
      (node (ref "D165") (pin "4") (pinfunction "G_4") (pintype "passive"))
      (node (ref "U8") (pin "10") (pinfunction "OUT5_10") (pintype "passive"))
    )
    (net (code "37") (name "Net-(D157-R)") (class "Default")
      (node (ref "D157") (pin "1") (pinfunction "R_1") (pintype "passive"))
      (node (ref "D158") (pin "1") (pinfunction "R_1") (pintype "passive"))
      (node (ref "D159") (pin "1") (pinfunction "R_1") (pintype "passive"))
      (node (ref "D160") (pin "1") (pinfunction "R_1") (pintype "passive"))
      (node (ref "D161") (pin "1") (pinfunction "R_1") (pintype "passive"))
      (node (ref "D162") (pin "1") (pinfunction "R_1") (pintype "passive"))
      (node (ref "D163") (pin "1") (pinfunction "R_1") (pintype "passive"))
      (node (ref "D164") (pin "1") (pinfunction "R_1") (pintype "passive"))
      (node (ref "D165") (pin "1") (pinfunction "R_1") (pintype "passive"))
      (node (ref "U8") (pin "8") (pinfunction "OUT3_8") (pintype "passive"))
    )
    (net (code "38") (name "Net-(D166-B)") (class "Default")
      (node (ref "D166") (pin "3") (pinfunction "B_3") (pintype "passive"))
      (node (ref "D167") (pin "3") (pinfunction "B_3") (pintype "passive"))
      (node (ref "D168") (pin "3") (pinfunction "B_3") (pintype "passive"))
      (node (ref "D169") (pin "3") (pinfunction "B_3") (pintype "passive"))
      (node (ref "D170") (pin "3") (pinfunction "B_3") (pintype "passive"))
      (node (ref "D171") (pin "3") (pinfunction "B_3") (pintype "passive"))
      (node (ref "D172") (pin "3") (pinfunction "B_3") (pintype "passive"))
      (node (ref "D173") (pin "3") (pinfunction "B_3") (pintype "passive"))
      (node (ref "D174") (pin "3") (pinfunction "B_3") (pintype "passive"))
      (node (ref "U8") (pin "12") (pinfunction "OUT7_12") (pintype "passive"))
    )
    (net (code "39") (name "Net-(D166-G)") (class "Default")
      (node (ref "D166") (pin "4") (pinfunction "G_4") (pintype "passive"))
      (node (ref "D167") (pin "4") (pinfunction "G_4") (pintype "passive"))
      (node (ref "D168") (pin "4") (pinfunction "G_4") (pintype "passive"))
      (node (ref "D169") (pin "4") (pinfunction "G_4") (pintype "passive"))
      (node (ref "D170") (pin "4") (pinfunction "G_4") (pintype "passive"))
      (node (ref "D171") (pin "4") (pinfunction "G_4") (pintype "passive"))
      (node (ref "D172") (pin "4") (pinfunction "G_4") (pintype "passive"))
      (node (ref "D173") (pin "4") (pinfunction "G_4") (pintype "passive"))
      (node (ref "D174") (pin "4") (pinfunction "G_4") (pintype "passive"))
      (node (ref "U8") (pin "13") (pinfunction "OUT8_13") (pintype "passive"))
    )
    (net (code "40") (name "Net-(D166-R)") (class "Default")
      (node (ref "D166") (pin "1") (pinfunction "R_1") (pintype "passive"))
      (node (ref "D167") (pin "1") (pinfunction "R_1") (pintype "passive"))
      (node (ref "D168") (pin "1") (pinfunction "R_1") (pintype "passive"))
      (node (ref "D169") (pin "1") (pinfunction "R_1") (pintype "passive"))
      (node (ref "D170") (pin "1") (pinfunction "R_1") (pintype "passive"))
      (node (ref "D171") (pin "1") (pinfunction "R_1") (pintype "passive"))
      (node (ref "D172") (pin "1") (pinfunction "R_1") (pintype "passive"))
      (node (ref "D173") (pin "1") (pinfunction "R_1") (pintype "passive"))
      (node (ref "D174") (pin "1") (pinfunction "R_1") (pintype "passive"))
      (node (ref "U8") (pin "11") (pinfunction "OUT6_11") (pintype "passive"))
    )
    (net (code "41") (name "Net-(D175-B)") (class "Default")
      (node (ref "D175") (pin "3") (pinfunction "B_3") (pintype "passive"))
      (node (ref "D176") (pin "3") (pinfunction "B_3") (pintype "passive"))
      (node (ref "D177") (pin "3") (pinfunction "B_3") (pintype "passive"))
      (node (ref "D178") (pin "3") (pinfunction "B_3") (pintype "passive"))
      (node (ref "D179") (pin "3") (pinfunction "B_3") (pintype "passive"))
      (node (ref "D180") (pin "3") (pinfunction "B_3") (pintype "passive"))
      (node (ref "D181") (pin "3") (pinfunction "B_3") (pintype "passive"))
      (node (ref "D182") (pin "3") (pinfunction "B_3") (pintype "passive"))
      (node (ref "D183") (pin "3") (pinfunction "B_3") (pintype "passive"))
      (node (ref "U8") (pin "15") (pinfunction "OUT10_15") (pintype "passive"))
    )
    (net (code "42") (name "Net-(D175-G)") (class "Default")
      (node (ref "D175") (pin "4") (pinfunction "G_4") (pintype "passive"))
      (node (ref "D176") (pin "4") (pinfunction "G_4") (pintype "passive"))
      (node (ref "D177") (pin "4") (pinfunction "G_4") (pintype "passive"))
      (node (ref "D178") (pin "4") (pinfunction "G_4") (pintype "passive"))
      (node (ref "D179") (pin "4") (pinfunction "G_4") (pintype "passive"))
      (node (ref "D180") (pin "4") (pinfunction "G_4") (pintype "passive"))
      (node (ref "D181") (pin "4") (pinfunction "G_4") (pintype "passive"))
      (node (ref "D182") (pin "4") (pinfunction "G_4") (pintype "passive"))
      (node (ref "D183") (pin "4") (pinfunction "G_4") (pintype "passive"))
      (node (ref "U8") (pin "16") (pinfunction "OUT11_16") (pintype "passive"))
    )
    (net (code "43") (name "Net-(D175-R)") (class "Default")
      (node (ref "D175") (pin "1") (pinfunction "R_1") (pintype "passive"))
      (node (ref "D176") (pin "1") (pinfunction "R_1") (pintype "passive"))
      (node (ref "D177") (pin "1") (pinfunction "R_1") (pintype "passive"))
      (node (ref "D178") (pin "1") (pinfunction "R_1") (pintype "passive"))
      (node (ref "D179") (pin "1") (pinfunction "R_1") (pintype "passive"))
      (node (ref "D180") (pin "1") (pinfunction "R_1") (pintype "passive"))
      (node (ref "D181") (pin "1") (pinfunction "R_1") (pintype "passive"))
      (node (ref "D182") (pin "1") (pinfunction "R_1") (pintype "passive"))
      (node (ref "D183") (pin "1") (pinfunction "R_1") (pintype "passive"))
      (node (ref "U8") (pin "14") (pinfunction "OUT9_14") (pintype "passive"))
    )
    (net (code "44") (name "Net-(D184-B)") (class "Default")
      (node (ref "D184") (pin "3") (pinfunction "B_3") (pintype "passive"))
      (node (ref "D185") (pin "3") (pinfunction "B_3") (pintype "passive"))
      (node (ref "D186") (pin "3") (pinfunction "B_3") (pintype "passive"))
      (node (ref "D187") (pin "3") (pinfunction "B_3") (pintype "passive"))
      (node (ref "D188") (pin "3") (pinfunction "B_3") (pintype "passive"))
      (node (ref "D189") (pin "3") (pinfunction "B_3") (pintype "passive"))
      (node (ref "D190") (pin "3") (pinfunction "B_3") (pintype "passive"))
      (node (ref "D191") (pin "3") (pinfunction "B_3") (pintype "passive"))
      (node (ref "D192") (pin "3") (pinfunction "B_3") (pintype "passive"))
      (node (ref "U9") (pin "6") (pinfunction "OUT1_6") (pintype "passive"))
    )
    (net (code "45") (name "Net-(D184-G)") (class "Default")
      (node (ref "D184") (pin "4") (pinfunction "G_4") (pintype "passive"))
      (node (ref "D185") (pin "4") (pinfunction "G_4") (pintype "passive"))
      (node (ref "D186") (pin "4") (pinfunction "G_4") (pintype "passive"))
      (node (ref "D187") (pin "4") (pinfunction "G_4") (pintype "passive"))
      (node (ref "D188") (pin "4") (pinfunction "G_4") (pintype "passive"))
      (node (ref "D189") (pin "4") (pinfunction "G_4") (pintype "passive"))
      (node (ref "D190") (pin "4") (pinfunction "G_4") (pintype "passive"))
      (node (ref "D191") (pin "4") (pinfunction "G_4") (pintype "passive"))
      (node (ref "D192") (pin "4") (pinfunction "G_4") (pintype "passive"))
      (node (ref "U9") (pin "7") (pinfunction "OUT2_7") (pintype "passive"))
    )
    (net (code "46") (name "Net-(D184-R)") (class "Default")
      (node (ref "D184") (pin "1") (pinfunction "R_1") (pintype "passive"))
      (node (ref "D185") (pin "1") (pinfunction "R_1") (pintype "passive"))
      (node (ref "D186") (pin "1") (pinfunction "R_1") (pintype "passive"))
      (node (ref "D187") (pin "1") (pinfunction "R_1") (pintype "passive"))
      (node (ref "D188") (pin "1") (pinfunction "R_1") (pintype "passive"))
      (node (ref "D189") (pin "1") (pinfunction "R_1") (pintype "passive"))
      (node (ref "D190") (pin "1") (pinfunction "R_1") (pintype "passive"))
      (node (ref "D191") (pin "1") (pinfunction "R_1") (pintype "passive"))
      (node (ref "D192") (pin "1") (pinfunction "R_1") (pintype "passive"))
      (node (ref "U9") (pin "5") (pinfunction "OUT0_5") (pintype "passive"))
    )
    (net (code "47") (name "Net-(D193-B)") (class "Default")
      (node (ref "D193") (pin "3") (pinfunction "B_3") (pintype "passive"))
      (node (ref "D194") (pin "3") (pinfunction "B_3") (pintype "passive"))
      (node (ref "D195") (pin "3") (pinfunction "B_3") (pintype "passive"))
      (node (ref "D196") (pin "3") (pinfunction "B_3") (pintype "passive"))
      (node (ref "D197") (pin "3") (pinfunction "B_3") (pintype "passive"))
      (node (ref "D198") (pin "3") (pinfunction "B_3") (pintype "passive"))
      (node (ref "D199") (pin "3") (pinfunction "B_3") (pintype "passive"))
      (node (ref "D200") (pin "3") (pinfunction "B_3") (pintype "passive"))
      (node (ref "D201") (pin "3") (pinfunction "B_3") (pintype "passive"))
      (node (ref "U9") (pin "9") (pinfunction "OUT4_9") (pintype "passive"))
    )
    (net (code "48") (name "Net-(D193-G)") (class "Default")
      (node (ref "D193") (pin "4") (pinfunction "G_4") (pintype "passive"))
      (node (ref "D194") (pin "4") (pinfunction "G_4") (pintype "passive"))
      (node (ref "D195") (pin "4") (pinfunction "G_4") (pintype "passive"))
      (node (ref "D196") (pin "4") (pinfunction "G_4") (pintype "passive"))
      (node (ref "D197") (pin "4") (pinfunction "G_4") (pintype "passive"))
      (node (ref "D198") (pin "4") (pinfunction "G_4") (pintype "passive"))
      (node (ref "D199") (pin "4") (pinfunction "G_4") (pintype "passive"))
      (node (ref "D200") (pin "4") (pinfunction "G_4") (pintype "passive"))
      (node (ref "D201") (pin "4") (pinfunction "G_4") (pintype "passive"))
      (node (ref "U9") (pin "10") (pinfunction "OUT5_10") (pintype "passive"))
    )
    (net (code "49") (name "Net-(D193-R)") (class "Default")
      (node (ref "D193") (pin "1") (pinfunction "R_1") (pintype "passive"))
      (node (ref "D194") (pin "1") (pinfunction "R_1") (pintype "passive"))
      (node (ref "D195") (pin "1") (pinfunction "R_1") (pintype "passive"))
      (node (ref "D196") (pin "1") (pinfunction "R_1") (pintype "passive"))
      (node (ref "D197") (pin "1") (pinfunction "R_1") (pintype "passive"))
      (node (ref "D198") (pin "1") (pinfunction "R_1") (pintype "passive"))
      (node (ref "D199") (pin "1") (pinfunction "R_1") (pintype "passive"))
      (node (ref "D200") (pin "1") (pinfunction "R_1") (pintype "passive"))
      (node (ref "D201") (pin "1") (pinfunction "R_1") (pintype "passive"))
      (node (ref "U9") (pin "8") (pinfunction "OUT3_8") (pintype "passive"))
    )
    (net (code "50") (name "Net-(D202-B)") (class "Default")
      (node (ref "D202") (pin "3") (pinfunction "B_3") (pintype "passive"))
      (node (ref "D203") (pin "3") (pinfunction "B_3") (pintype "passive"))
      (node (ref "D204") (pin "3") (pinfunction "B_3") (pintype "passive"))
      (node (ref "D205") (pin "3") (pinfunction "B_3") (pintype "passive"))
      (node (ref "D206") (pin "3") (pinfunction "B_3") (pintype "passive"))
      (node (ref "D207") (pin "3") (pinfunction "B_3") (pintype "passive"))
      (node (ref "D208") (pin "3") (pinfunction "B_3") (pintype "passive"))
      (node (ref "D209") (pin "3") (pinfunction "B_3") (pintype "passive"))
      (node (ref "D210") (pin "3") (pinfunction "B_3") (pintype "passive"))
      (node (ref "U9") (pin "12") (pinfunction "OUT7_12") (pintype "passive"))
    )
    (net (code "51") (name "Net-(D202-G)") (class "Default")
      (node (ref "D202") (pin "4") (pinfunction "G_4") (pintype "passive"))
      (node (ref "D203") (pin "4") (pinfunction "G_4") (pintype "passive"))
      (node (ref "D204") (pin "4") (pinfunction "G_4") (pintype "passive"))
      (node (ref "D205") (pin "4") (pinfunction "G_4") (pintype "passive"))
      (node (ref "D206") (pin "4") (pinfunction "G_4") (pintype "passive"))
      (node (ref "D207") (pin "4") (pinfunction "G_4") (pintype "passive"))
      (node (ref "D208") (pin "4") (pinfunction "G_4") (pintype "passive"))
      (node (ref "D209") (pin "4") (pinfunction "G_4") (pintype "passive"))
      (node (ref "D210") (pin "4") (pinfunction "G_4") (pintype "passive"))
      (node (ref "U9") (pin "13") (pinfunction "OUT8_13") (pintype "passive"))
    )
    (net (code "52") (name "Net-(D202-R)") (class "Default")
      (node (ref "D202") (pin "1") (pinfunction "R_1") (pintype "passive"))
      (node (ref "D203") (pin "1") (pinfunction "R_1") (pintype "passive"))
      (node (ref "D204") (pin "1") (pinfunction "R_1") (pintype "passive"))
      (node (ref "D205") (pin "1") (pinfunction "R_1") (pintype "passive"))
      (node (ref "D206") (pin "1") (pinfunction "R_1") (pintype "passive"))
      (node (ref "D207") (pin "1") (pinfunction "R_1") (pintype "passive"))
      (node (ref "D208") (pin "1") (pinfunction "R_1") (pintype "passive"))
      (node (ref "D209") (pin "1") (pinfunction "R_1") (pintype "passive"))
      (node (ref "D210") (pin "1") (pinfunction "R_1") (pintype "passive"))
      (node (ref "U9") (pin "11") (pinfunction "OUT6_11") (pintype "passive"))
    )
    (net (code "53") (name "Net-(D211-B)") (class "Default")
      (node (ref "D211") (pin "3") (pinfunction "B_3") (pintype "passive"))
      (node (ref "D212") (pin "3") (pinfunction "B_3") (pintype "passive"))
      (node (ref "D213") (pin "3") (pinfunction "B_3") (pintype "passive"))
      (node (ref "D214") (pin "3") (pinfunction "B_3") (pintype "passive"))
      (node (ref "D215") (pin "3") (pinfunction "B_3") (pintype "passive"))
      (node (ref "D216") (pin "3") (pinfunction "B_3") (pintype "passive"))
      (node (ref "D217") (pin "3") (pinfunction "B_3") (pintype "passive"))
      (node (ref "D218") (pin "3") (pinfunction "B_3") (pintype "passive"))
      (node (ref "U9") (pin "15") (pinfunction "OUT10_15") (pintype "passive"))
    )
    (net (code "54") (name "Net-(D211-G)") (class "Default")
      (node (ref "D211") (pin "4") (pinfunction "G_4") (pintype "passive"))
      (node (ref "D212") (pin "4") (pinfunction "G_4") (pintype "passive"))
      (node (ref "D213") (pin "4") (pinfunction "G_4") (pintype "passive"))
      (node (ref "D214") (pin "4") (pinfunction "G_4") (pintype "passive"))
      (node (ref "D215") (pin "4") (pinfunction "G_4") (pintype "passive"))
      (node (ref "D216") (pin "4") (pinfunction "G_4") (pintype "passive"))
      (node (ref "D217") (pin "4") (pinfunction "G_4") (pintype "passive"))
      (node (ref "D218") (pin "4") (pinfunction "G_4") (pintype "passive"))
      (node (ref "U9") (pin "16") (pinfunction "OUT11_16") (pintype "passive"))
    )
    (net (code "55") (name "Net-(D211-R)") (class "Default")
      (node (ref "D211") (pin "1") (pinfunction "R_1") (pintype "passive"))
      (node (ref "D212") (pin "1") (pinfunction "R_1") (pintype "passive"))
      (node (ref "D213") (pin "1") (pinfunction "R_1") (pintype "passive"))
      (node (ref "D214") (pin "1") (pinfunction "R_1") (pintype "passive"))
      (node (ref "D215") (pin "1") (pinfunction "R_1") (pintype "passive"))
      (node (ref "D216") (pin "1") (pinfunction "R_1") (pintype "passive"))
      (node (ref "D217") (pin "1") (pinfunction "R_1") (pintype "passive"))
      (node (ref "D218") (pin "1") (pinfunction "R_1") (pintype "passive"))
      (node (ref "U9") (pin "14") (pinfunction "OUT9_14") (pintype "passive"))
    )
    (net (code "56") (name "Net-(Q3-G)") (class "Default")
      (node (ref "Q3") (pin "1") (pinfunction "G_1") (pintype "passive"))
      (node (ref "R60") (pin "2") (pinfunction "2_2") (pintype "passive"))
      (node (ref "R75") (pin "1") (pinfunction "1_1") (pintype "passive"))
    )
    (net (code "57") (name "Net-(Q4-G)") (class "Default")
      (node (ref "Q4") (pin "1") (pinfunction "G_1") (pintype "passive"))
      (node (ref "R61") (pin "2") (pinfunction "2_2") (pintype "passive"))
      (node (ref "R62") (pin "2") (pinfunction "2_2") (pintype "passive"))
    )
    (net (code "58") (name "Net-(Q5-G)") (class "Default")
      (node (ref "Q5") (pin "1") (pinfunction "G_1") (pintype "passive"))
      (node (ref "R63") (pin "2") (pinfunction "2_2") (pintype "passive"))
      (node (ref "R64") (pin "2") (pinfunction "2_2") (pintype "passive"))
    )
    (net (code "59") (name "Net-(Q6-G)") (class "Default")
      (node (ref "Q6") (pin "1") (pinfunction "G_1") (pintype "passive"))
      (node (ref "R65") (pin "2") (pinfunction "2_2") (pintype "passive"))
      (node (ref "R66") (pin "2") (pinfunction "2_2") (pintype "passive"))
    )
    (net (code "60") (name "Net-(Q7-G)") (class "Default")
      (node (ref "Q7") (pin "1") (pinfunction "G_1") (pintype "passive"))
      (node (ref "R67") (pin "2") (pinfunction "2_2") (pintype "passive"))
      (node (ref "R68") (pin "2") (pinfunction "2_2") (pintype "passive"))
    )
    (net (code "61") (name "Net-(Q8-G)") (class "Default")
      (node (ref "Q8") (pin "1") (pinfunction "G_1") (pintype "passive"))
      (node (ref "R69") (pin "2") (pinfunction "2_2") (pintype "passive"))
      (node (ref "R70") (pin "2") (pinfunction "2_2") (pintype "passive"))
    )
    (net (code "62") (name "Net-(Q9-G)") (class "Default")
      (node (ref "Q9") (pin "1") (pinfunction "G_1") (pintype "passive"))
      (node (ref "R71") (pin "2") (pinfunction "2_2") (pintype "passive"))
      (node (ref "R72") (pin "2") (pinfunction "2_2") (pintype "passive"))
    )
    (net (code "63") (name "Net-(Q10-G)") (class "Default")
      (node (ref "Q10") (pin "1") (pinfunction "G_1") (pintype "passive"))
      (node (ref "R73") (pin "2") (pinfunction "2_2") (pintype "passive"))
      (node (ref "R74") (pin "2") (pinfunction "2_2") (pintype "passive"))
    )
    (net (code "64") (name "Net-(Q12-G)") (class "Default")
      (node (ref "Q12") (pin "1") (pinfunction "G_1") (pintype "passive"))
      (node (ref "R82") (pin "2") (pinfunction "2_2") (pintype "passive"))
      (node (ref "R83") (pin "2") (pinfunction "2_2") (pintype "passive"))
    )
    (net (code "65") (name "Net-(U7-SDI)") (class "Default")
      (node (ref "U7") (pin "14") (pinfunction "SDI_14") (pintype "input"))
      (node (ref "U8") (pin "22") (pinfunction "SO_22") (pintype "passive"))
    )
    (net (code "66") (name "Net-(U8-Iref)") (class "Default")
      (node (ref "R78") (pin "2") (pinfunction "2_2") (pintype "passive"))
      (node (ref "U8") (pin "23") (pinfunction "Iref_23") (pintype "passive"))
    )
    (net (code "67") (name "Net-(U8-SI)") (class "Default")
      (node (ref "U8") (pin "2") (pinfunction "SI_2") (pintype "passive"))
      (node (ref "U9") (pin "22") (pinfunction "SO_22") (pintype "passive"))
    )
    (net (code "68") (name "Net-(U9-Iref)") (class "Default")
      (node (ref "R79") (pin "2") (pinfunction "2_2") (pintype "passive"))
      (node (ref "U9") (pin "23") (pinfunction "Iref_23") (pintype "passive"))
    )
    (net (code "69") (name "unconnected-(U9-OUT12-Pad17)") (class "Default")
      (node (ref "U9") (pin "17") (pinfunction "OUT12_17") (pintype "passive+no_connect"))
    )
    (net (code "70") (name "unconnected-(U9-OUT13-Pad18)") (class "Default")
      (node (ref "U9") (pin "18") (pinfunction "OUT13_18") (pintype "passive+no_connect"))
    )
    (net (code "71") (name "unconnected-(U9-OUT14-Pad19)") (class "Default")
      (node (ref "U9") (pin "19") (pinfunction "OUT14_19") (pintype "passive+no_connect"))
    )
    (net (code "72") (name "unconnected-(U9-OUT15-Pad20)") (class "Default")
      (node (ref "U9") (pin "20") (pinfunction "OUT15_20") (pintype "passive+no_connect"))
    )
  )
)
